# esp32buscam_02.net
KiCad netlist of a schematic drawn in EAGLE
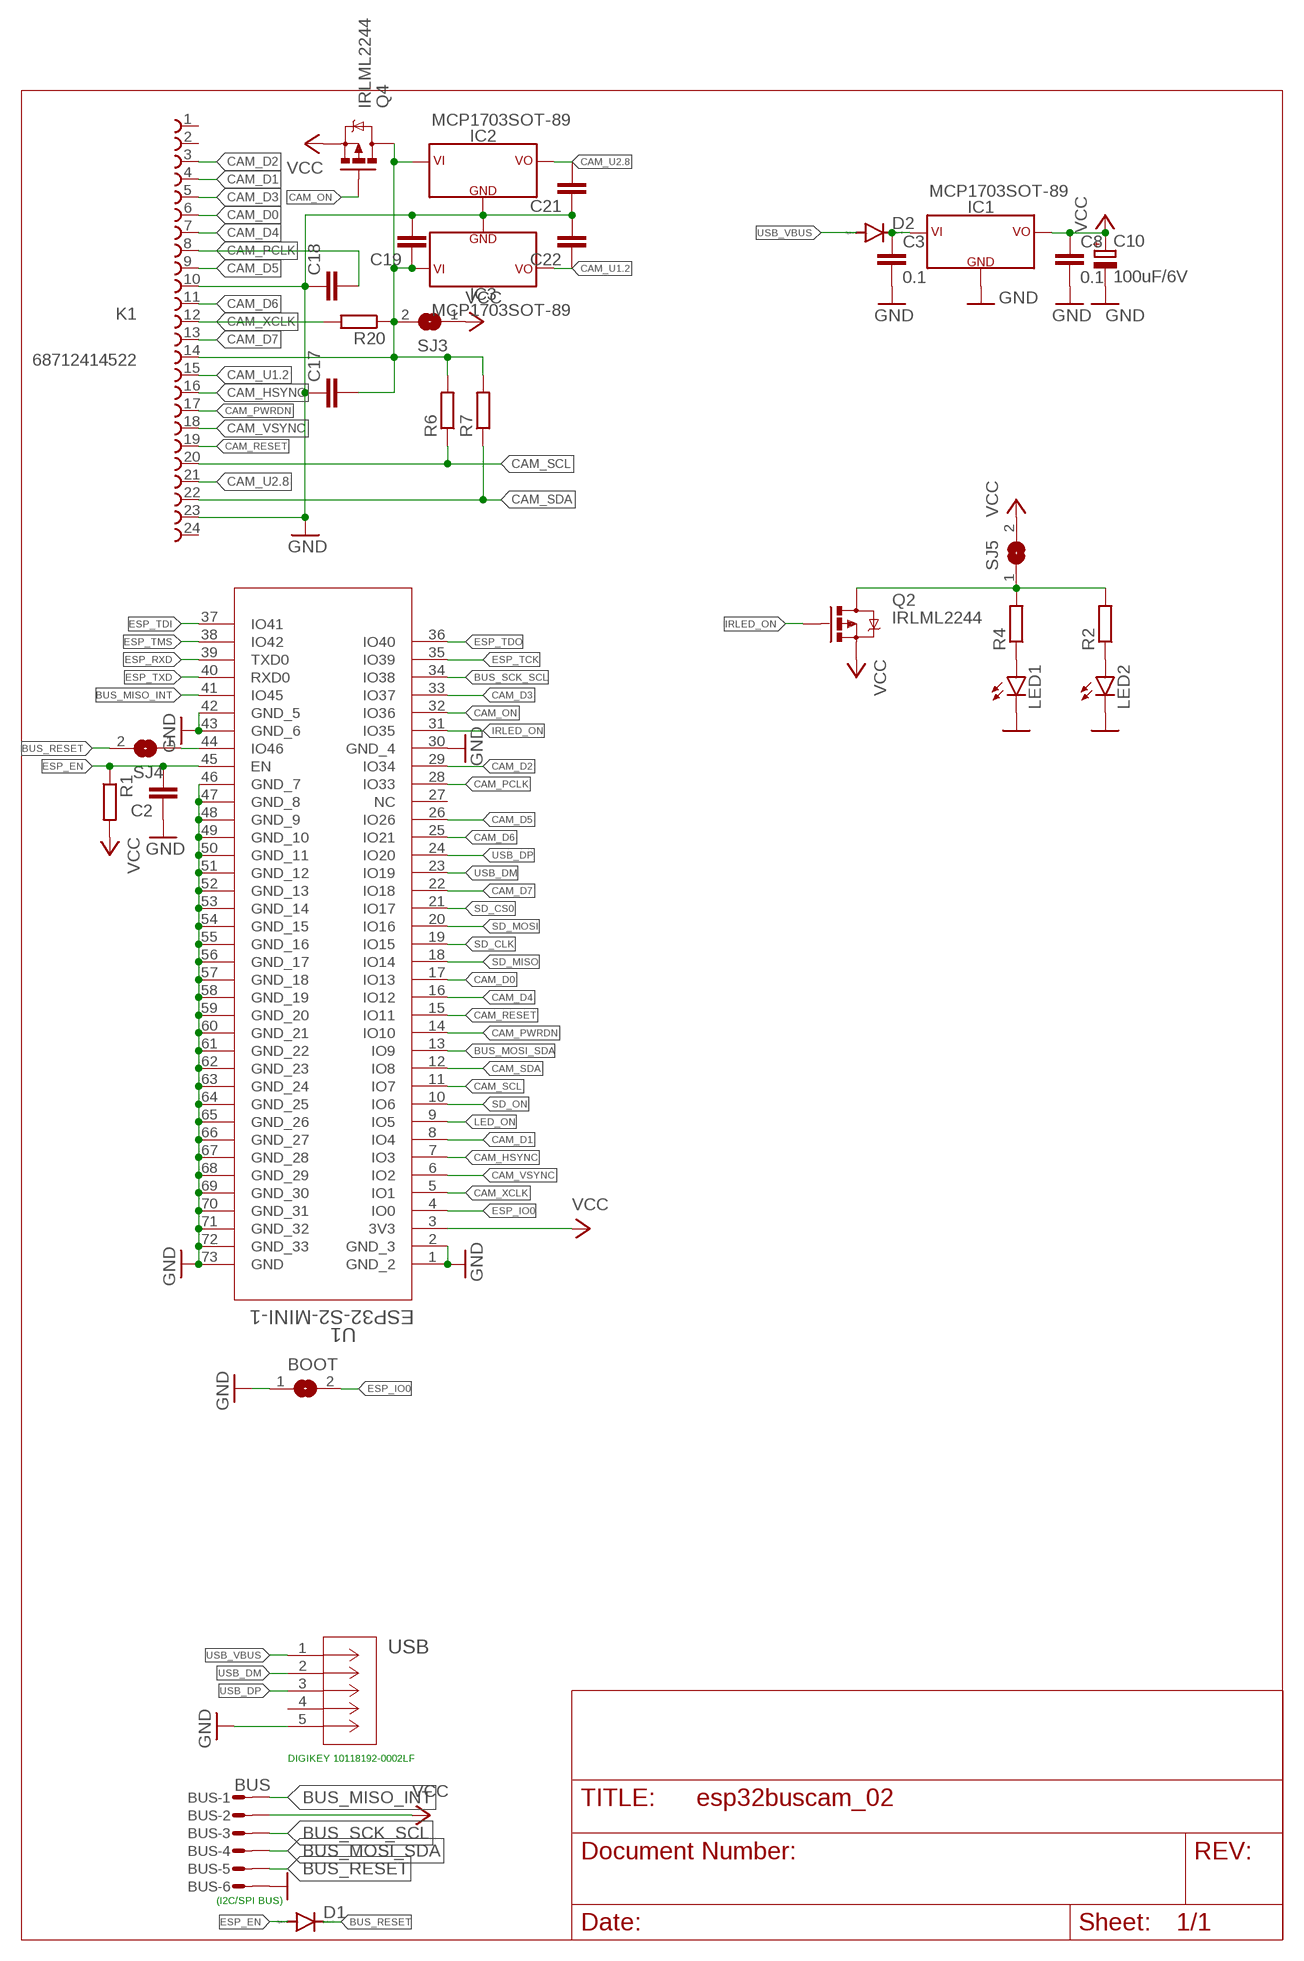
[diagram p0: schematic, sheet 1]

(export (version "E")
  (design (tool "Eeschema 10.0.6"))
  (components
    (comp (ref "BOOT")
      (value "SJ")
      (footprint "eagle-import:SJ")
      (libsource (lib "eagle-import") (part "SJ"))
    )
    (comp (ref "BUS")
      (value "BUS")
      (footprint "eagle-import:MICROMATCH-6SMD")
      (libsource (lib "eagle-import") (part "MICROMATCH-6SMD"))
    )
    (comp (ref "C2")
      (value "C-EUC0603")
      (footprint "eagle-import:C0603")
      (libsource (lib "eagle-import") (part "rcl_334_C-EUC0603"))
    )
    (comp (ref "C3")
      (value "0.1")
      (footprint "eagle-import:C0805")
      (libsource (lib "eagle-import") (part "C-EUC0805"))
    )
    (comp (ref "C8")
      (value "0.1")
      (footprint "eagle-import:C0805")
      (libsource (lib "eagle-import") (part "C-EUC0805"))
    )
    (comp (ref "C10")
      (value "100uF/6V")
      (footprint "eagle-import:B_3528-21R")
      (libsource (lib "eagle-import") (part "CPOL-EUB/3528-21R"))
    )
    (comp (ref "C17")
      (value "C-EUC0603")
      (footprint "eagle-import:C0603")
      (libsource (lib "eagle-import") (part "rcl_334_C-EUC0603"))
    )
    (comp (ref "C18")
      (value "C-EUC0603")
      (footprint "eagle-import:C0603")
      (libsource (lib "eagle-import") (part "rcl_334_C-EUC0603"))
    )
    (comp (ref "C19")
      (value "C-EUC0603")
      (footprint "eagle-import:C0603")
      (libsource (lib "eagle-import") (part "rcl_334_C-EUC0603"))
    )
    (comp (ref "C21")
      (value "C-EUC0603")
      (footprint "eagle-import:C0603")
      (libsource (lib "eagle-import") (part "rcl_334_C-EUC0603"))
    )
    (comp (ref "C22")
      (value "C-EUC0603")
      (footprint "eagle-import:C0603")
      (libsource (lib "eagle-import") (part "rcl_334_C-EUC0603"))
    )
    (comp (ref "D1")
      (value "DIODE-MINIMELF")
      (footprint "eagle-import:MINIMELF")
      (libsource (lib "eagle-import") (part "DIODE-MINIMELF"))
    )
    (comp (ref "D2")
      (value "DIODE-MINIMELF")
      (footprint "eagle-import:MINIMELF")
      (libsource (lib "eagle-import") (part "DIODE-MINIMELF"))
    )
    (comp (ref "IC1")
      (value "MCP1703SOT-89")
      (footprint "eagle-import:SOT89")
      (libsource (lib "eagle-import") (part "MCP1703SOT-89"))
    )
    (comp (ref "IC2")
      (value "MCP1703SOT-89")
      (footprint "eagle-import:SOT89")
      (libsource (lib "eagle-import") (part "MCP1703SOT-89"))
    )
    (comp (ref "IC3")
      (value "MCP1703SOT-89")
      (footprint "eagle-import:SOT89")
      (libsource (lib "eagle-import") (part "MCP1703SOT-89"))
    )
    (comp (ref "K1")
      (value "68712414522")
      (footprint "eagle-import:68712414522")
      (libsource (lib "eagle-import") (part "68712414522"))
    )
    (comp (ref "LED1")
      (value "LED5MM")
      (footprint "eagle-import:LED5MM")
      (libsource (lib "eagle-import") (part "LED5MM"))
    )
    (comp (ref "LED2")
      (value "LED5MM")
      (footprint "eagle-import:LED5MM")
      (libsource (lib "eagle-import") (part "LED5MM"))
    )
    (comp (ref "Q2")
      (value "IRLML2244")
      (footprint "eagle-import:SOT23-3")
      (libsource (lib "eagle-import") (part "MOSFET-PCHANNELIRLML2244"))
    )
    (comp (ref "Q4")
      (value "IRLML2244")
      (footprint "eagle-import:SOT23-3")
      (libsource (lib "eagle-import") (part "MOSFET-PCHANNELIRLML2244"))
    )
    (comp (ref "R1")
      (value "R-EU_R0603")
      (footprint "eagle-import:R0603")
      (libsource (lib "eagle-import") (part "R-EU_R0603"))
    )
    (comp (ref "R2")
      (value "R-EU_R0402")
      (footprint "eagle-import:R0402")
      (libsource (lib "eagle-import") (part "R-EU_R0402"))
    )
    (comp (ref "R4")
      (value "R-EU_R0402")
      (footprint "eagle-import:R0402")
      (libsource (lib "eagle-import") (part "R-EU_R0402"))
    )
    (comp (ref "R6")
      (value "R-EU_R0603")
      (footprint "eagle-import:R0603")
      (libsource (lib "eagle-import") (part "R-EU_R0603"))
    )
    (comp (ref "R7")
      (value "R-EU_R0603")
      (footprint "eagle-import:R0603")
      (libsource (lib "eagle-import") (part "R-EU_R0603"))
    )
    (comp (ref "R20")
      (value "R-EU_R0603")
      (footprint "eagle-import:R0603")
      (libsource (lib "eagle-import") (part "R-EU_R0603"))
    )
    (comp (ref "SJ3") (value "SJ") (footprint "eagle-import:SJ") (libsource (lib "eagle-import") (part "SJ")))
    (comp (ref "SJ4") (value "SJ") (footprint "eagle-import:SJ") (libsource (lib "eagle-import") (part "SJ")))
    (comp (ref "SJ5") (value "SJ") (footprint "eagle-import:SJ") (libsource (lib "eagle-import") (part "SJ")))
    (comp (ref "U1")
      (value "ESP32-S2-MINI-1")
      (footprint "eagle-import:QFN60_ESP32-S2-MINI-1_EXP")
      (fields (field (name "COPYRIGHT") "Copyright (C) 2018 Accelerated Designs. All rights reserved"))
      (libsource (lib "eagle-import") (part "ESP32-S2-MINI-1"))
    )
    (comp (ref "USB")
      (value "10118192-0002LF")
      (footprint "eagle-import:CONN_10118192-0002LF_AMP")
      (fields (field (name "COPYRIGHT") "Copyright (C) 2018 Accelerated Designs. All rights reserved"))
      (libsource (lib "eagle-import") (part "10118192-0002LF"))
    )
  )
  (nets
    (net (code "1") (name "BUS_MISO_INT") (class "Default")
      (node (ref "BUS") (pin "1") (pinfunction "S_1") (pintype "passive"))
      (node (ref "U1") (pin "41") (pinfunction "IO45_41") (pintype "bidirectional"))
    )
    (net (code "2") (name "BUS_MOSI_SDA") (class "Default")
      (node (ref "BUS") (pin "4") (pinfunction "S_4") (pintype "passive"))
      (node (ref "U1") (pin "13") (pinfunction "IO9_13") (pintype "bidirectional"))
    )
    (net (code "3") (name "BUS_RESET") (class "Default")
      (node (ref "BUS") (pin "5") (pinfunction "S_5") (pintype "passive"))
      (node (ref "D1") (pin "C") (pinfunction "C_C") (pintype "passive"))
      (node (ref "SJ4") (pin "2") (pinfunction "2_2") (pintype "passive"))
    )
    (net (code "4") (name "BUS_SCK_SCL") (class "Default")
      (node (ref "BUS") (pin "3") (pinfunction "S_3") (pintype "passive"))
      (node (ref "U1") (pin "34") (pinfunction "IO38_34") (pintype "bidirectional"))
    )
    (net (code "5") (name "CAM_D0") (class "Default")
      (node (ref "K1") (pin "6") (pinfunction "6_6") (pintype "passive"))
      (node (ref "U1") (pin "17") (pinfunction "IO13_17") (pintype "bidirectional"))
    )
    (net (code "6") (name "CAM_D1") (class "Default")
      (node (ref "K1") (pin "4") (pinfunction "4_4") (pintype "passive"))
      (node (ref "U1") (pin "8") (pinfunction "IO4_8") (pintype "bidirectional"))
    )
    (net (code "7") (name "CAM_D2") (class "Default")
      (node (ref "K1") (pin "3") (pinfunction "3_3") (pintype "passive"))
      (node (ref "U1") (pin "29") (pinfunction "IO34_29") (pintype "bidirectional"))
    )
    (net (code "8") (name "CAM_D3") (class "Default")
      (node (ref "K1") (pin "5") (pinfunction "5_5") (pintype "passive"))
      (node (ref "U1") (pin "33") (pinfunction "IO37_33") (pintype "bidirectional"))
    )
    (net (code "9") (name "CAM_D4") (class "Default")
      (node (ref "K1") (pin "7") (pinfunction "7_7") (pintype "passive"))
      (node (ref "U1") (pin "16") (pinfunction "IO12_16") (pintype "bidirectional"))
    )
    (net (code "10") (name "CAM_D5") (class "Default")
      (node (ref "K1") (pin "9") (pinfunction "9_9") (pintype "passive"))
      (node (ref "U1") (pin "26") (pinfunction "IO26_26") (pintype "bidirectional"))
    )
    (net (code "11") (name "CAM_D6") (class "Default")
      (node (ref "K1") (pin "11") (pinfunction "11_11") (pintype "passive"))
      (node (ref "U1") (pin "25") (pinfunction "IO21_25") (pintype "bidirectional"))
    )
    (net (code "12") (name "CAM_D7") (class "Default")
      (node (ref "K1") (pin "13") (pinfunction "13_13") (pintype "passive"))
      (node (ref "U1") (pin "22") (pinfunction "IO18_22") (pintype "bidirectional"))
    )
    (net (code "13") (name "CAM_HSYNC") (class "Default")
      (node (ref "K1") (pin "16") (pinfunction "16_16") (pintype "passive"))
      (node (ref "U1") (pin "7") (pinfunction "IO3_7") (pintype "bidirectional"))
    )
    (net (code "14") (name "CAM_ON") (class "Default")
      (node (ref "Q4") (pin "1") (pinfunction "G_1") (pintype "passive"))
      (node (ref "U1") (pin "32") (pinfunction "IO36_32") (pintype "bidirectional"))
    )
    (net (code "15") (name "CAM_PCLK") (class "Default")
      (node (ref "C18") (pin "2") (pinfunction "2_2") (pintype "passive"))
      (node (ref "K1") (pin "8") (pinfunction "8_8") (pintype "passive"))
      (node (ref "U1") (pin "28") (pinfunction "IO33_28") (pintype "bidirectional"))
    )
    (net (code "16") (name "CAM_PWRDN") (class "Default")
      (node (ref "K1") (pin "17") (pinfunction "17_17") (pintype "passive"))
      (node (ref "U1") (pin "14") (pinfunction "IO10_14") (pintype "bidirectional"))
    )
    (net (code "17") (name "CAM_RESET") (class "Default")
      (node (ref "K1") (pin "19") (pinfunction "19_19") (pintype "passive"))
      (node (ref "U1") (pin "15") (pinfunction "IO11_15") (pintype "bidirectional"))
    )
    (net (code "18") (name "CAM_SCL") (class "Default")
      (node (ref "K1") (pin "20") (pinfunction "20_20") (pintype "passive"))
      (node (ref "R6") (pin "1") (pinfunction "1_1") (pintype "passive"))
      (node (ref "U1") (pin "11") (pinfunction "IO7_11") (pintype "bidirectional"))
    )
    (net (code "19") (name "CAM_SDA") (class "Default")
      (node (ref "K1") (pin "22") (pinfunction "22_22") (pintype "passive"))
      (node (ref "R7") (pin "1") (pinfunction "1_1") (pintype "passive"))
      (node (ref "U1") (pin "12") (pinfunction "IO8_12") (pintype "bidirectional"))
    )
    (net (code "20") (name "CAM_U1.2") (class "Default")
      (node (ref "C22") (pin "1") (pinfunction "1_1") (pintype "passive"))
      (node (ref "IC3") (pin "3") (pinfunction "VCC_3") (pintype "power_in"))
      (node (ref "K1") (pin "15") (pinfunction "15_15") (pintype "passive"))
    )
    (net (code "21") (name "CAM_U2.8") (class "Default")
      (node (ref "C21") (pin "2") (pinfunction "2_2") (pintype "passive"))
      (node (ref "IC2") (pin "3") (pinfunction "VCC_3") (pintype "power_in"))
      (node (ref "K1") (pin "21") (pinfunction "21_21") (pintype "passive"))
    )
    (net (code "22") (name "CAM_VSYNC") (class "Default")
      (node (ref "K1") (pin "18") (pinfunction "18_18") (pintype "passive"))
      (node (ref "U1") (pin "6") (pinfunction "IO2_6") (pintype "bidirectional"))
    )
    (net (code "23") (name "CAM_XCLK") (class "Default")
      (node (ref "K1") (pin "12") (pinfunction "12_12") (pintype "passive"))
      (node (ref "R20") (pin "2") (pinfunction "2_2") (pintype "passive"))
      (node (ref "U1") (pin "5") (pinfunction "IO1_5") (pintype "bidirectional"))
    )
    (net (code "24") (name "ESP_EN") (class "Default")
      (node (ref "C2") (pin "2") (pinfunction "2_2") (pintype "passive"))
      (node (ref "D1") (pin "A") (pinfunction "A_A") (pintype "passive"))
      (node (ref "R1") (pin "1") (pinfunction "1_1") (pintype "passive"))
      (node (ref "U1") (pin "45") (pinfunction "EN_45") (pintype "passive"))
    )
    (net (code "25") (name "ESP_IO0") (class "Default")
      (node (ref "BOOT") (pin "2") (pinfunction "2_2") (pintype "passive"))
      (node (ref "U1") (pin "4") (pinfunction "IO0_4") (pintype "bidirectional"))
    )
    (net (code "26") (name "ESP_RXD") (class "Default")
      (node (ref "U1") (pin "39") (pinfunction "TXD0_39") (pintype "bidirectional"))
    )
    (net (code "27") (name "ESP_TCK") (class "Default")
      (node (ref "U1") (pin "35") (pinfunction "IO39_35") (pintype "bidirectional"))
    )
    (net (code "28") (name "ESP_TDI") (class "Default")
      (node (ref "U1") (pin "37") (pinfunction "IO41_37") (pintype "bidirectional"))
    )
    (net (code "29") (name "ESP_TDO") (class "Default")
      (node (ref "U1") (pin "36") (pinfunction "IO40_36") (pintype "bidirectional"))
    )
    (net (code "30") (name "ESP_TMS") (class "Default")
      (node (ref "U1") (pin "38") (pinfunction "IO42_38") (pintype "bidirectional"))
    )
    (net (code "31") (name "ESP_TXD") (class "Default")
      (node (ref "U1") (pin "40") (pinfunction "RXD0_40") (pintype "bidirectional"))
    )
    (net (code "32") (name "GND") (class "Default")
      (node (ref "BOOT") (pin "1") (pinfunction "1_1") (pintype "passive"))
      (node (ref "BUS") (pin "6") (pinfunction "S_6") (pintype "passive"))
      (node (ref "C10") (pin "-") (pinfunction "-_-") (pintype "passive"))
      (node (ref "C17") (pin "1") (pinfunction "1_1") (pintype "passive"))
      (node (ref "C18") (pin "1") (pinfunction "1_1") (pintype "passive"))
      (node (ref "C19") (pin "2") (pinfunction "2_2") (pintype "passive"))
      (node (ref "C2") (pin "1") (pinfunction "1_1") (pintype "passive"))
      (node (ref "C21") (pin "1") (pinfunction "1_1") (pintype "passive"))
      (node (ref "C22") (pin "2") (pinfunction "2_2") (pintype "passive"))
      (node (ref "C3") (pin "2") (pinfunction "2_2") (pintype "passive"))
      (node (ref "C8") (pin "2") (pinfunction "2_2") (pintype "passive"))
      (node (ref "IC1") (pin "1") (pinfunction "GND_1") (pintype "power_in"))
      (node (ref "IC2") (pin "1") (pinfunction "GND_1") (pintype "power_in"))
      (node (ref "IC3") (pin "1") (pinfunction "GND_1") (pintype "power_in"))
      (node (ref "K1") (pin "10") (pinfunction "10_10") (pintype "passive"))
      (node (ref "K1") (pin "23") (pinfunction "23_23") (pintype "passive"))
      (node (ref "LED1") (pin "K") (pinfunction "C_K") (pintype "passive"))
      (node (ref "LED2") (pin "K") (pinfunction "C_K") (pintype "passive"))
      (node (ref "U1") (pin "1") (pinfunction "GND_2_1") (pintype "passive"))
      (node (ref "U1") (pin "2") (pinfunction "GND_3_2") (pintype "passive"))
      (node (ref "U1") (pin "30") (pinfunction "GND_4_30") (pintype "passive"))
      (node (ref "U1") (pin "42") (pinfunction "GND_5_42") (pintype "passive"))
      (node (ref "U1") (pin "43") (pinfunction "GND_6_43") (pintype "passive"))
      (node (ref "U1") (pin "46") (pinfunction "GND_7_46") (pintype "passive"))
      (node (ref "U1") (pin "47") (pinfunction "GND_8_47") (pintype "passive"))
      (node (ref "U1") (pin "48") (pinfunction "GND_9_48") (pintype "passive"))
      (node (ref "U1") (pin "49") (pinfunction "GND_10_49") (pintype "passive"))
      (node (ref "U1") (pin "50") (pinfunction "GND_11_50") (pintype "passive"))
      (node (ref "U1") (pin "51") (pinfunction "GND_12_51") (pintype "passive"))
      (node (ref "U1") (pin "52") (pinfunction "GND_13_52") (pintype "passive"))
      (node (ref "U1") (pin "53") (pinfunction "GND_14_53") (pintype "passive"))
      (node (ref "U1") (pin "54") (pinfunction "GND_15_54") (pintype "passive"))
      (node (ref "U1") (pin "55") (pinfunction "GND_16_55") (pintype "passive"))
      (node (ref "U1") (pin "56") (pinfunction "GND_17_56") (pintype "passive"))
      (node (ref "U1") (pin "57") (pinfunction "GND_18_57") (pintype "passive"))
      (node (ref "U1") (pin "58") (pinfunction "GND_19_58") (pintype "passive"))
      (node (ref "U1") (pin "59") (pinfunction "GND_20_59") (pintype "passive"))
      (node (ref "U1") (pin "60") (pinfunction "GND_21_60") (pintype "passive"))
      (node (ref "U1") (pin "61") (pinfunction "GND_22_61") (pintype "passive"))
      (node (ref "U1") (pin "62") (pinfunction "GND_23_62") (pintype "passive"))
      (node (ref "U1") (pin "63") (pinfunction "GND_24_63") (pintype "passive"))
      (node (ref "U1") (pin "64") (pinfunction "GND_25_64") (pintype "passive"))
      (node (ref "U1") (pin "65") (pinfunction "GND_26_65") (pintype "passive"))
      (node (ref "U1") (pin "66") (pinfunction "GND_27_66") (pintype "passive"))
      (node (ref "U1") (pin "67") (pinfunction "GND_28_67") (pintype "passive"))
      (node (ref "U1") (pin "68") (pinfunction "GND_29_68") (pintype "passive"))
      (node (ref "U1") (pin "69") (pinfunction "GND_30_69") (pintype "passive"))
      (node (ref "U1") (pin "70") (pinfunction "GND_31_70") (pintype "passive"))
      (node (ref "U1") (pin "71") (pinfunction "GND_32_71") (pintype "passive"))
      (node (ref "U1") (pin "72") (pinfunction "GND_33_72") (pintype "passive"))
      (node (ref "U1") (pin "73") (pinfunction "GND_73") (pintype "passive"))
      (node (ref "USB") (pin "5") (pinfunction "5_5") (pintype "passive"))
    )
    (net (code "33") (name "IRLED_ON") (class "Default")
      (node (ref "Q2") (pin "1") (pinfunction "G_1") (pintype "passive"))
      (node (ref "U1") (pin "31") (pinfunction "IO35_31") (pintype "bidirectional"))
    )
    (net (code "34") (name "LED_ON") (class "Default")
      (node (ref "U1") (pin "9") (pinfunction "IO5_9") (pintype "bidirectional"))
    )
    (net (code "35") (name "Net-(C3-Pad1)") (class "Default")
      (node (ref "C3") (pin "1") (pinfunction "1_1") (pintype "passive"))
      (node (ref "D2") (pin "C") (pinfunction "C_C") (pintype "passive"))
      (node (ref "IC1") (pin "2") (pinfunction "VIN_2") (pintype "power_in"))
      (node (ref "IC1") (pin "4") (pinfunction "VIN_4") (pintype "power_in"))
    )
    (net (code "36") (name "Net-(LED1-PadA)") (class "Default")
      (node (ref "LED1") (pin "A") (pinfunction "A_A") (pintype "passive"))
      (node (ref "R4") (pin "1") (pinfunction "1_1") (pintype "passive"))
    )
    (net (code "37") (name "Net-(LED2-PadA)") (class "Default")
      (node (ref "LED2") (pin "A") (pinfunction "A_A") (pintype "passive"))
      (node (ref "R2") (pin "1") (pinfunction "1_1") (pintype "passive"))
    )
    (net (code "38") (name "Net-(Q2-D)") (class "Default")
      (node (ref "Q2") (pin "3") (pinfunction "D_3") (pintype "passive"))
      (node (ref "R2") (pin "2") (pinfunction "2_2") (pintype "passive"))
      (node (ref "R4") (pin "2") (pinfunction "2_2") (pintype "passive"))
      (node (ref "SJ5") (pin "1") (pinfunction "1_1") (pintype "passive"))
    )
    (net (code "39") (name "Net-(Q4-D)") (class "Default")
      (node (ref "C17") (pin "2") (pinfunction "2_2") (pintype "passive"))
      (node (ref "C19") (pin "1") (pinfunction "1_1") (pintype "passive"))
      (node (ref "IC2") (pin "2") (pinfunction "VIN_2") (pintype "power_in"))
      (node (ref "IC2") (pin "4") (pinfunction "VIN_4") (pintype "power_in"))
      (node (ref "IC3") (pin "2") (pinfunction "VIN_2") (pintype "power_in"))
      (node (ref "IC3") (pin "4") (pinfunction "VIN_4") (pintype "power_in"))
      (node (ref "K1") (pin "14") (pinfunction "14_14") (pintype "passive"))
      (node (ref "Q4") (pin "3") (pinfunction "D_3") (pintype "passive"))
      (node (ref "R20") (pin "1") (pinfunction "1_1") (pintype "passive"))
      (node (ref "R6") (pin "2") (pinfunction "2_2") (pintype "passive"))
      (node (ref "R7") (pin "2") (pinfunction "2_2") (pintype "passive"))
      (node (ref "SJ3") (pin "2") (pinfunction "2_2") (pintype "passive"))
    )
    (net (code "40") (name "Net-(U1-IO46)") (class "Default")
      (node (ref "SJ4") (pin "1") (pinfunction "1_1") (pintype "passive"))
      (node (ref "U1") (pin "44") (pinfunction "IO46_44") (pintype "bidirectional"))
    )
    (net (code "41") (name "SD_CLK") (class "Default")
      (node (ref "U1") (pin "19") (pinfunction "IO15_19") (pintype "bidirectional"))
    )
    (net (code "42") (name "SD_CS0") (class "Default")
      (node (ref "U1") (pin "21") (pinfunction "IO17_21") (pintype "bidirectional"))
    )
    (net (code "43") (name "SD_MISO") (class "Default")
      (node (ref "U1") (pin "18") (pinfunction "IO14_18") (pintype "bidirectional"))
    )
    (net (code "44") (name "SD_MOSI") (class "Default")
      (node (ref "U1") (pin "20") (pinfunction "IO16_20") (pintype "bidirectional"))
    )
    (net (code "45") (name "SD_ON") (class "Default")
      (node (ref "U1") (pin "10") (pinfunction "IO6_10") (pintype "bidirectional"))
    )
    (net (code "46") (name "USB_DM") (class "Default")
      (node (ref "U1") (pin "23") (pinfunction "IO19_23") (pintype "bidirectional"))
      (node (ref "USB") (pin "2") (pinfunction "2_2") (pintype "passive"))
    )
    (net (code "47") (name "USB_DP") (class "Default")
      (node (ref "U1") (pin "24") (pinfunction "IO20_24") (pintype "bidirectional"))
      (node (ref "USB") (pin "3") (pinfunction "3_3") (pintype "passive"))
    )
    (net (code "48") (name "USB_VBUS") (class "Default")
      (node (ref "D2") (pin "A") (pinfunction "A_A") (pintype "passive"))
      (node (ref "USB") (pin "1") (pinfunction "1_1") (pintype "passive"))
    )
    (net (code "49") (name "VCC") (class "Default")
      (node (ref "BUS") (pin "2") (pinfunction "S_2") (pintype "passive"))
      (node (ref "C10") (pin "+") (pinfunction "+_+") (pintype "passive"))
      (node (ref "C8") (pin "1") (pinfunction "1_1") (pintype "passive"))
      (node (ref "IC1") (pin "3") (pinfunction "VCC_3") (pintype "power_in"))
      (node (ref "Q2") (pin "2") (pinfunction "S_2") (pintype "passive"))
      (node (ref "Q4") (pin "2") (pinfunction "S_2") (pintype "passive"))
      (node (ref "R1") (pin "2") (pinfunction "2_2") (pintype "passive"))
      (node (ref "SJ3") (pin "1") (pinfunction "1_1") (pintype "passive"))
      (node (ref "SJ5") (pin "2") (pinfunction "2_2") (pintype "passive"))
      (node (ref "U1") (pin "3") (pinfunction "3V3_3") (pintype "passive"))
    )
    (net (code "50") (name "unconnected-(K1-Pad1)") (class "Default")
      (node (ref "K1") (pin "1") (pinfunction "1_1") (pintype "passive"))
    )
    (net (code "51") (name "unconnected-(K1-Pad2)") (class "Default")
      (node (ref "K1") (pin "2") (pinfunction "2_2") (pintype "passive"))
    )
    (net (code "52") (name "unconnected-(K1-Pad24)") (class "Default")
      (node (ref "K1") (pin "24") (pinfunction "24_24") (pintype "passive"))
    )
    (net (code "53") (name "unconnected-(U1-NC-Pad27)") (class "Default")
      (node (ref "U1") (pin "27") (pinfunction "NC_27") (pintype "no_connect"))
    )
    (net (code "54") (name "unconnected-(USB-Pad4)") (class "Default")
      (node (ref "USB") (pin "4") (pinfunction "4_4") (pintype "passive"))
    )
  )
)
